# SDriveARM.net
KiCad netlist of a schematic drawn in EAGLE
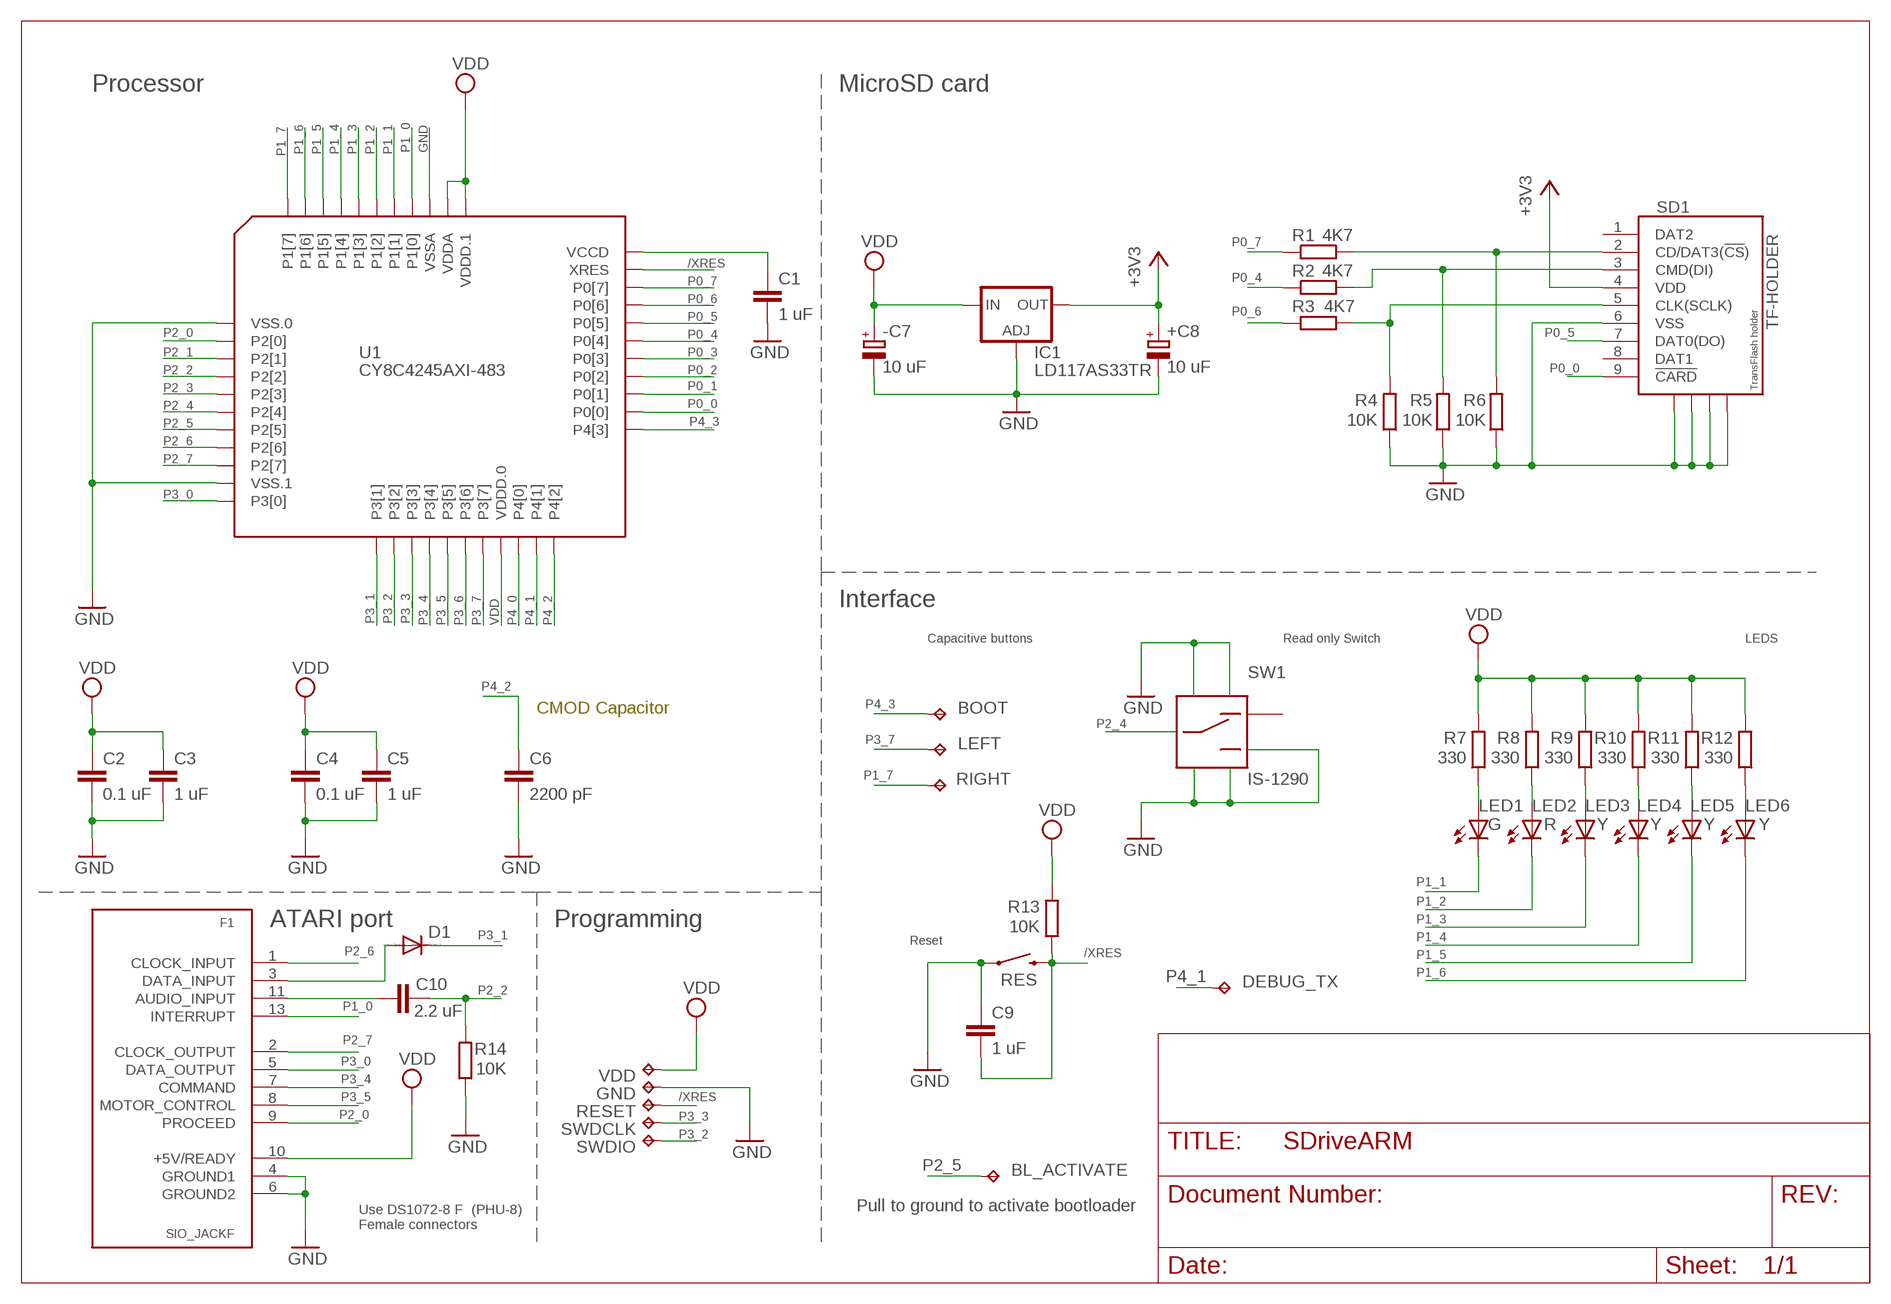
[diagram p0: schematic, sheet 1]

(export (version "E")
  (design (tool "Eeschema 10.0.6"))
  (components
    (comp (ref "+C8")
      (value "10 uF")
      (footprint "eagle-import:A_3216-18W")
      (libsource (lib "eagle-import") (part "CPOL-EUA/3216-18W"))
    )
    (comp (ref "-C7")
      (value "10 uF")
      (footprint "eagle-import:A_3216-18W")
      (libsource (lib "eagle-import") (part "CPOL-EUA/3216-18W"))
    )
    (comp (ref "BL_ACTIVATE")
      (value "TPB1,27")
      (footprint "eagle-import:B1,27")
      (libsource (lib "eagle-import") (part "TPB1,27"))
    )
    (comp (ref "BOOT")
      (value "TPTP20SQ")
      (footprint "eagle-import:TP20SQ")
      (libsource (lib "eagle-import") (part "TPTP20SQ"))
    )
    (comp (ref "C1")
      (value "1 uF")
      (footprint "eagle-import:C0603")
      (libsource (lib "eagle-import") (part "C-EUC0603"))
    )
    (comp (ref "C2")
      (value "0.1 uF")
      (footprint "eagle-import:C0603")
      (libsource (lib "eagle-import") (part "C-EUC0603"))
    )
    (comp (ref "C3")
      (value "1 uF")
      (footprint "eagle-import:C0603")
      (libsource (lib "eagle-import") (part "C-EUC0603"))
    )
    (comp (ref "C4")
      (value "0.1 uF")
      (footprint "eagle-import:C0603")
      (libsource (lib "eagle-import") (part "C-EUC0603"))
    )
    (comp (ref "C5")
      (value "1 uF")
      (footprint "eagle-import:C0603")
      (libsource (lib "eagle-import") (part "C-EUC0603"))
    )
    (comp (ref "C6")
      (value "2200 pF")
      (footprint "eagle-import:C0603")
      (libsource (lib "eagle-import") (part "C-EUC0603"))
    )
    (comp (ref "C9")
      (value "1 uF")
      (footprint "eagle-import:C0603")
      (libsource (lib "eagle-import") (part "C-EUC0603"))
    )
    (comp (ref "C10")
      (value "2.2 uF")
      (footprint "eagle-import:C0603")
      (libsource (lib "eagle-import") (part "C-EUC0603"))
    )
    (comp (ref "D1")
      (value "MBR0520LT")
      (footprint "eagle-import:SOD123")
      (libsource (lib "eagle-import") (part "MBR0520LT"))
    )
    (comp (ref "DEBUG_TX")
      (value "TPB1,27")
      (footprint "eagle-import:B1,27")
      (libsource (lib "eagle-import") (part "TPB1,27"))
    )
    (comp (ref "F1")
      (value "SIO_JACKF")
      (footprint "eagle-import:SIO_JACK_F")
      (libsource (lib "eagle-import") (part "SIO_JACKF"))
    )
    (comp (ref "GND")
      (value "TPB1,27")
      (footprint "eagle-import:B1,27")
      (libsource (lib "eagle-import") (part "TPB1,27"))
    )
    (comp (ref "IC1")
      (value "LD117AS33TR")
      (footprint "eagle-import:SOT223")
      (libsource (lib "eagle-import") (part "LD117A?S33TR"))
    )
    (comp (ref "LED1")
      (value "G")
      (footprint "eagle-import:SML0805")
      (libsource (lib "eagle-import") (part "LEDSML0805"))
    )
    (comp (ref "LED2")
      (value "R")
      (footprint "eagle-import:SML0805")
      (libsource (lib "eagle-import") (part "LEDSML0805"))
    )
    (comp (ref "LED3")
      (value "Y")
      (footprint "eagle-import:SML0805")
      (libsource (lib "eagle-import") (part "LEDSML0805"))
    )
    (comp (ref "LED4")
      (value "Y")
      (footprint "eagle-import:SML0805")
      (libsource (lib "eagle-import") (part "LEDSML0805"))
    )
    (comp (ref "LED5")
      (value "Y")
      (footprint "eagle-import:SML0805")
      (libsource (lib "eagle-import") (part "LEDSML0805"))
    )
    (comp (ref "LED6")
      (value "Y")
      (footprint "eagle-import:SML0805")
      (libsource (lib "eagle-import") (part "LEDSML0805"))
    )
    (comp (ref "LEFT")
      (value "TPTP20SQ")
      (footprint "eagle-import:TP20SQ")
      (libsource (lib "eagle-import") (part "TPTP20SQ"))
    )
    (comp (ref "R1")
      (value "4K7")
      (footprint "eagle-import:R0603")
      (libsource (lib "eagle-import") (part "R-EU_R0603"))
    )
    (comp (ref "R2")
      (value "4K7")
      (footprint "eagle-import:R0603")
      (libsource (lib "eagle-import") (part "R-EU_R0603"))
    )
    (comp (ref "R3")
      (value "4K7")
      (footprint "eagle-import:R0603")
      (libsource (lib "eagle-import") (part "R-EU_R0603"))
    )
    (comp (ref "R4")
      (value "10K")
      (footprint "eagle-import:R0603")
      (libsource (lib "eagle-import") (part "R-EU_R0603"))
    )
    (comp (ref "R5")
      (value "10K")
      (footprint "eagle-import:R0603")
      (libsource (lib "eagle-import") (part "R-EU_R0603"))
    )
    (comp (ref "R6")
      (value "10K")
      (footprint "eagle-import:R0603")
      (libsource (lib "eagle-import") (part "R-EU_R0603"))
    )
    (comp (ref "R7")
      (value "330")
      (footprint "eagle-import:R0603")
      (libsource (lib "eagle-import") (part "R-EU_R0603"))
    )
    (comp (ref "R8")
      (value "330")
      (footprint "eagle-import:R0603")
      (libsource (lib "eagle-import") (part "R-EU_R0603"))
    )
    (comp (ref "R9")
      (value "330")
      (footprint "eagle-import:R0603")
      (libsource (lib "eagle-import") (part "R-EU_R0603"))
    )
    (comp (ref "R10")
      (value "330")
      (footprint "eagle-import:R0603")
      (libsource (lib "eagle-import") (part "R-EU_R0603"))
    )
    (comp (ref "R11")
      (value "330")
      (footprint "eagle-import:R0603")
      (libsource (lib "eagle-import") (part "R-EU_R0603"))
    )
    (comp (ref "R12")
      (value "330")
      (footprint "eagle-import:R0603")
      (libsource (lib "eagle-import") (part "R-EU_R0603"))
    )
    (comp (ref "R13")
      (value "10K")
      (footprint "eagle-import:R0603")
      (libsource (lib "eagle-import") (part "R-EU_R0603"))
    )
    (comp (ref "R14")
      (value "10K")
      (footprint "eagle-import:R0603")
      (libsource (lib "eagle-import") (part "R-EU_R0603"))
    )
    (comp (ref "RES")
      (value "SWITCH-MOMENTARY-2")
      (footprint "eagle-import:TACTILE_SWITCH_TALL")
      (libsource (lib "eagle-import") (part "SWITCH-MOMENTARY-2"))
    )
    (comp (ref "RESET")
      (value "TPB1,27")
      (footprint "eagle-import:B1,27")
      (libsource (lib "eagle-import") (part "TPB1,27"))
    )
    (comp (ref "RIGHT")
      (value "TPTP20SQ")
      (footprint "eagle-import:TP20SQ")
      (libsource (lib "eagle-import") (part "TPTP20SQ"))
    )
    (comp (ref "SD1")
      (value "TF-HOLDER")
      (footprint "eagle-import:TF-PULL")
      (libsource (lib "eagle-import") (part "TF-HOLDER"))
    )
    (comp (ref "SW1")
      (value "IS-1290")
      (footprint "eagle-import:IS-1290")
      (libsource (lib "eagle-import") (part "IS-1290"))
    )
    (comp (ref "SWDCLK")
      (value "TPB1,27")
      (footprint "eagle-import:B1,27")
      (libsource (lib "eagle-import") (part "TPB1,27"))
    )
    (comp (ref "SWDIO")
      (value "TPB1,27")
      (footprint "eagle-import:B1,27")
      (libsource (lib "eagle-import") (part "TPB1,27"))
    )
    (comp (ref "U1")
      (value "CY8C4245AXI-483")
      (footprint "eagle-import:TQFP44")
      (libsource (lib "eagle-import") (part "CY8C4245AXI-483"))
    )
    (comp (ref "VDD")
      (value "TPB1,27")
      (footprint "eagle-import:B1,27")
      (libsource (lib "eagle-import") (part "TPB1,27"))
    )
  )
  (nets
    (net (code "1") (name "+3V3") (class "Default")
      (node (ref "+C8") (pin "+") (pinfunction "+_+") (pintype "passive"))
      (node (ref "IC1") (pin "4") (pinfunction "OUT_4") (pintype "passive"))
      (node (ref "SD1") (pin "4") (pinfunction "VDD_4") (pintype "power_in"))
    )
    (net (code "2") (name "/P0_0") (class "Default")
      (node (ref "SD1") (pin "9") (pinfunction "~{CARD}_9") (pintype "passive"))
      (node (ref "U1") (pin "24") (pinfunction "P0[0]_24") (pintype "bidirectional"))
    )
    (net (code "3") (name "/P0_1") (class "Default")
      (node (ref "U1") (pin "25") (pinfunction "P0[1]_25") (pintype "bidirectional"))
    )
    (net (code "4") (name "/P0_2") (class "Default")
      (node (ref "U1") (pin "26") (pinfunction "P0[2]_26") (pintype "bidirectional"))
    )
    (net (code "5") (name "/P0_3") (class "Default")
      (node (ref "U1") (pin "27") (pinfunction "P0[3]_27") (pintype "bidirectional"))
    )
    (net (code "6") (name "/P0_4") (class "Default")
      (node (ref "R2") (pin "1") (pinfunction "1_1") (pintype "passive"))
      (node (ref "U1") (pin "28") (pinfunction "P0[4]_28") (pintype "bidirectional"))
    )
    (net (code "7") (name "/P0_5") (class "Default")
      (node (ref "SD1") (pin "7") (pinfunction "DAT0(DO)_7") (pintype "bidirectional"))
      (node (ref "U1") (pin "29") (pinfunction "P0[5]_29") (pintype "bidirectional"))
    )
    (net (code "8") (name "/P0_6") (class "Default")
      (node (ref "R3") (pin "1") (pinfunction "1_1") (pintype "passive"))
      (node (ref "U1") (pin "30") (pinfunction "P0[6]_30") (pintype "bidirectional"))
    )
    (net (code "9") (name "/P0_7") (class "Default")
      (node (ref "R1") (pin "1") (pinfunction "1_1") (pintype "passive"))
      (node (ref "U1") (pin "31") (pinfunction "P0[7]_31") (pintype "bidirectional"))
    )
    (net (code "10") (name "/P1_0") (class "Default")
      (node (ref "F1") (pin "13") (pinfunction "INTERRUPT_13") (pintype "output"))
      (node (ref "U1") (pin "37") (pinfunction "P1[0]_37") (pintype "bidirectional"))
    )
    (net (code "11") (name "/P1_1") (class "Default")
      (node (ref "LED1") (pin "C") (pinfunction "C_C") (pintype "passive"))
      (node (ref "U1") (pin "38") (pinfunction "P1[1]_38") (pintype "bidirectional"))
    )
    (net (code "12") (name "/P1_2") (class "Default")
      (node (ref "LED2") (pin "C") (pinfunction "C_C") (pintype "passive"))
      (node (ref "U1") (pin "39") (pinfunction "P1[2]_39") (pintype "bidirectional"))
    )
    (net (code "13") (name "/P1_3") (class "Default")
      (node (ref "LED3") (pin "C") (pinfunction "C_C") (pintype "passive"))
      (node (ref "U1") (pin "40") (pinfunction "P1[3]_40") (pintype "bidirectional"))
    )
    (net (code "14") (name "/P1_4") (class "Default")
      (node (ref "LED4") (pin "C") (pinfunction "C_C") (pintype "passive"))
      (node (ref "U1") (pin "41") (pinfunction "P1[4]_41") (pintype "bidirectional"))
    )
    (net (code "15") (name "/P1_5") (class "Default")
      (node (ref "LED5") (pin "C") (pinfunction "C_C") (pintype "passive"))
      (node (ref "U1") (pin "42") (pinfunction "P1[5]_42") (pintype "bidirectional"))
    )
    (net (code "16") (name "/P1_6") (class "Default")
      (node (ref "LED6") (pin "C") (pinfunction "C_C") (pintype "passive"))
      (node (ref "U1") (pin "43") (pinfunction "P1[6]_43") (pintype "bidirectional"))
    )
    (net (code "17") (name "/P1_7") (class "Default")
      (node (ref "RIGHT") (pin "TP") (pinfunction "TP_TP") (pintype "input"))
      (node (ref "U1") (pin "44") (pinfunction "P1[7]_44") (pintype "bidirectional"))
    )
    (net (code "18") (name "/P2_0") (class "Default")
      (node (ref "F1") (pin "9") (pinfunction "PROCEED_9") (pintype "bidirectional"))
      (node (ref "U1") (pin "2") (pinfunction "P2[0]_2") (pintype "bidirectional"))
    )
    (net (code "19") (name "/P2_1") (class "Default")
      (node (ref "U1") (pin "3") (pinfunction "P2[1]_3") (pintype "bidirectional"))
    )
    (net (code "20") (name "/P2_2") (class "Default")
      (node (ref "C10") (pin "1") (pinfunction "1_1") (pintype "passive"))
      (node (ref "R14") (pin "2") (pinfunction "2_2") (pintype "passive"))
      (node (ref "U1") (pin "4") (pinfunction "P2[2]_4") (pintype "bidirectional"))
    )
    (net (code "21") (name "/P2_3") (class "Default")
      (node (ref "U1") (pin "5") (pinfunction "P2[3]_5") (pintype "bidirectional"))
    )
    (net (code "22") (name "/P2_4") (class "Default")
      (node (ref "SW1") (pin "COMMON") (pinfunction "COMMON_COMMON") (pintype "bidirectional"))
      (node (ref "U1") (pin "6") (pinfunction "P2[4]_6") (pintype "bidirectional"))
    )
    (net (code "23") (name "/P2_5") (class "Default")
      (node (ref "BL_ACTIVATE") (pin "TP") (pinfunction "TP_TP") (pintype "input"))
      (node (ref "U1") (pin "7") (pinfunction "P2[5]_7") (pintype "bidirectional"))
    )
    (net (code "24") (name "/P2_6") (class "Default")
      (node (ref "F1") (pin "1") (pinfunction "CLOCK_INPUT_1") (pintype "output"))
      (node (ref "U1") (pin "8") (pinfunction "P2[6]_8") (pintype "bidirectional"))
    )
    (net (code "25") (name "/P2_7") (class "Default")
      (node (ref "F1") (pin "2") (pinfunction "CLOCK_OUTPUT_2") (pintype "input"))
      (node (ref "U1") (pin "9") (pinfunction "P2[7]_9") (pintype "bidirectional"))
    )
    (net (code "26") (name "/P3_0") (class "Default")
      (node (ref "F1") (pin "5") (pinfunction "DATA_OUTPUT_5") (pintype "input"))
      (node (ref "U1") (pin "11") (pinfunction "P3[0]_11") (pintype "bidirectional"))
    )
    (net (code "27") (name "/P3_1") (class "Default")
      (node (ref "D1") (pin "C") (pinfunction "C_C") (pintype "passive"))
      (node (ref "U1") (pin "12") (pinfunction "P3[1]_12") (pintype "bidirectional"))
    )
    (net (code "28") (name "/P3_2") (class "Default")
      (node (ref "SWDIO") (pin "TP") (pinfunction "TP_TP") (pintype "input"))
      (node (ref "U1") (pin "13") (pinfunction "P3[2]_13") (pintype "bidirectional"))
    )
    (net (code "29") (name "/P3_3") (class "Default")
      (node (ref "SWDCLK") (pin "TP") (pinfunction "TP_TP") (pintype "input"))
      (node (ref "U1") (pin "14") (pinfunction "P3[3]_14") (pintype "bidirectional"))
    )
    (net (code "30") (name "/P3_4") (class "Default")
      (node (ref "F1") (pin "7") (pinfunction "COMMAND_7") (pintype "input"))
      (node (ref "U1") (pin "15") (pinfunction "P3[4]_15") (pintype "bidirectional"))
    )
    (net (code "31") (name "/P3_5") (class "Default")
      (node (ref "F1") (pin "8") (pinfunction "MOTOR_CONTROL_8") (pintype "input"))
      (node (ref "U1") (pin "16") (pinfunction "P3[5]_16") (pintype "bidirectional"))
    )
    (net (code "32") (name "/P3_6") (class "Default")
      (node (ref "U1") (pin "17") (pinfunction "P3[6]_17") (pintype "bidirectional"))
    )
    (net (code "33") (name "/P3_7") (class "Default")
      (node (ref "LEFT") (pin "TP") (pinfunction "TP_TP") (pintype "input"))
      (node (ref "U1") (pin "18") (pinfunction "P3[7]_18") (pintype "bidirectional"))
    )
    (net (code "34") (name "/P4_0") (class "Default")
      (node (ref "U1") (pin "20") (pinfunction "P4[0]_20") (pintype "bidirectional"))
    )
    (net (code "35") (name "/P4_1") (class "Default")
      (node (ref "DEBUG_TX") (pin "TP") (pinfunction "TP_TP") (pintype "input"))
      (node (ref "U1") (pin "21") (pinfunction "P4[1]_21") (pintype "bidirectional"))
    )
    (net (code "36") (name "/P4_2") (class "Default")
      (node (ref "C6") (pin "1") (pinfunction "1_1") (pintype "passive"))
      (node (ref "U1") (pin "22") (pinfunction "P4[2]_22") (pintype "bidirectional"))
    )
    (net (code "37") (name "/P4_3") (class "Default")
      (node (ref "BOOT") (pin "TP") (pinfunction "TP_TP") (pintype "input"))
      (node (ref "U1") (pin "23") (pinfunction "P4[3]_23") (pintype "bidirectional"))
    )
    (net (code "38") (name "/{slash}XRES") (class "Default")
      (node (ref "C9") (pin "2") (pinfunction "2_2") (pintype "passive"))
      (node (ref "R13") (pin "1") (pinfunction "1_1") (pintype "passive"))
      (node (ref "RES") (pin "B2") (pinfunction "2_B2") (pintype "passive"))
      (node (ref "RESET") (pin "TP") (pinfunction "TP_TP") (pintype "input"))
      (node (ref "U1") (pin "32") (pinfunction "XRES_32") (pintype "bidirectional"))
    )
    (net (code "39") (name "GND") (class "Default")
      (node (ref "+C8") (pin "-") (pinfunction "-_-") (pintype "passive"))
      (node (ref "-C7") (pin "-") (pinfunction "-_-") (pintype "passive"))
      (node (ref "C1") (pin "2") (pinfunction "2_2") (pintype "passive"))
      (node (ref "C2") (pin "2") (pinfunction "2_2") (pintype "passive"))
      (node (ref "C3") (pin "2") (pinfunction "2_2") (pintype "passive"))
      (node (ref "C4") (pin "2") (pinfunction "2_2") (pintype "passive"))
      (node (ref "C5") (pin "2") (pinfunction "2_2") (pintype "passive"))
      (node (ref "C6") (pin "2") (pinfunction "2_2") (pintype "passive"))
      (node (ref "C9") (pin "1") (pinfunction "1_1") (pintype "passive"))
      (node (ref "F1") (pin "4") (pinfunction "GROUND1_4") (pintype "power_in"))
      (node (ref "F1") (pin "6") (pinfunction "GROUND2_6") (pintype "power_in"))
      (node (ref "GND") (pin "TP") (pinfunction "TP_TP") (pintype "input"))
      (node (ref "IC1") (pin "1") (pinfunction "ADJ_1") (pintype "input"))
      (node (ref "R14") (pin "1") (pinfunction "1_1") (pintype "passive"))
      (node (ref "R4") (pin "1") (pinfunction "1_1") (pintype "passive"))
      (node (ref "R5") (pin "1") (pinfunction "1_1") (pintype "passive"))
      (node (ref "R6") (pin "1") (pinfunction "1_1") (pintype "passive"))
      (node (ref "RES") (pin "A2") (pinfunction "1_A2") (pintype "passive"))
      (node (ref "SD1") (pin "6") (pinfunction "VSS_6") (pintype "power_in"))
      (node (ref "SD1") (pin "S1") (pinfunction "S1_S1") (pintype "passive"))
      (node (ref "SD1") (pin "S2") (pinfunction "S2_S2") (pintype "passive"))
      (node (ref "SD1") (pin "S3") (pinfunction "S3_S3") (pintype "passive"))
      (node (ref "SD1") (pin "S4") (pinfunction "S4_S4") (pintype "passive"))
      (node (ref "SW1") (pin "POS2") (pinfunction "POS2_POS2") (pintype "bidirectional"))
      (node (ref "SW1") (pin "SHIELD$1") (pinfunction "P$4_SHIELD$1") (pintype "bidirectional"))
      (node (ref "SW1") (pin "SHIELD$2") (pinfunction "P$7_SHIELD$2") (pintype "bidirectional"))
      (node (ref "SW1") (pin "SHIELD$3") (pinfunction "P$5_SHIELD$3") (pintype "bidirectional"))
      (node (ref "SW1") (pin "SHIELD$4") (pinfunction "P$6_SHIELD$4") (pintype "bidirectional"))
      (node (ref "U1") (pin "1") (pinfunction "VSS.0_1") (pintype "power_in"))
      (node (ref "U1") (pin "10") (pinfunction "VSS.1_10") (pintype "power_in"))
      (node (ref "U1") (pin "36") (pinfunction "VSSA_36") (pintype "power_in"))
    )
    (net (code "40") (name "Net-(F1-AUDIO_INPUT)") (class "Default")
      (node (ref "C10") (pin "2") (pinfunction "2_2") (pintype "passive"))
      (node (ref "F1") (pin "11") (pinfunction "AUDIO_INPUT_11") (pintype "output"))
    )
    (net (code "41") (name "Net-(F1-DATA_INPUT)") (class "Default")
      (node (ref "D1") (pin "A") (pinfunction "A_A") (pintype "passive"))
      (node (ref "F1") (pin "3") (pinfunction "DATA_INPUT_3") (pintype "output"))
    )
    (net (code "42") (name "Net-(LED1-PadA)") (class "Default")
      (node (ref "LED1") (pin "A") (pinfunction "A_A") (pintype "passive"))
      (node (ref "R7") (pin "1") (pinfunction "1_1") (pintype "passive"))
    )
    (net (code "43") (name "Net-(LED2-PadA)") (class "Default")
      (node (ref "LED2") (pin "A") (pinfunction "A_A") (pintype "passive"))
      (node (ref "R8") (pin "1") (pinfunction "1_1") (pintype "passive"))
    )
    (net (code "44") (name "Net-(LED3-PadA)") (class "Default")
      (node (ref "LED3") (pin "A") (pinfunction "A_A") (pintype "passive"))
      (node (ref "R9") (pin "1") (pinfunction "1_1") (pintype "passive"))
    )
    (net (code "45") (name "Net-(LED4-PadA)") (class "Default")
      (node (ref "LED4") (pin "A") (pinfunction "A_A") (pintype "passive"))
      (node (ref "R10") (pin "1") (pinfunction "1_1") (pintype "passive"))
    )
    (net (code "46") (name "Net-(LED5-PadA)") (class "Default")
      (node (ref "LED5") (pin "A") (pinfunction "A_A") (pintype "passive"))
      (node (ref "R11") (pin "1") (pinfunction "1_1") (pintype "passive"))
    )
    (net (code "47") (name "Net-(LED6-PadA)") (class "Default")
      (node (ref "LED6") (pin "A") (pinfunction "A_A") (pintype "passive"))
      (node (ref "R12") (pin "1") (pinfunction "1_1") (pintype "passive"))
    )
    (net (code "48") (name "Net-(SD1-CD{slash}DAT3(~{CS}))") (class "Default")
      (node (ref "R1") (pin "2") (pinfunction "2_2") (pintype "passive"))
      (node (ref "R6") (pin "2") (pinfunction "2_2") (pintype "passive"))
      (node (ref "SD1") (pin "2") (pinfunction "CD/DAT3(~{CS})_2") (pintype "bidirectional"))
    )
    (net (code "49") (name "Net-(SD1-CLK(SCLK))") (class "Default")
      (node (ref "R3") (pin "2") (pinfunction "2_2") (pintype "passive"))
      (node (ref "R4") (pin "2") (pinfunction "2_2") (pintype "passive"))
      (node (ref "SD1") (pin "5") (pinfunction "CLK(SCLK)_5") (pintype "input"))
    )
    (net (code "50") (name "Net-(SD1-CMD(DI))") (class "Default")
      (node (ref "R2") (pin "2") (pinfunction "2_2") (pintype "passive"))
      (node (ref "R5") (pin "2") (pinfunction "2_2") (pintype "passive"))
      (node (ref "SD1") (pin "3") (pinfunction "CMD(DI)_3") (pintype "bidirectional"))
    )
    (net (code "51") (name "Net-(U1-VCCD)") (class "Default")
      (node (ref "C1") (pin "1") (pinfunction "1_1") (pintype "passive"))
      (node (ref "U1") (pin "33") (pinfunction "VCCD_33") (pintype "power_in"))
    )
    (net (code "52") (name "VDD") (class "Default")
      (node (ref "-C7") (pin "+") (pinfunction "+_+") (pintype "passive"))
      (node (ref "C2") (pin "1") (pinfunction "1_1") (pintype "passive"))
      (node (ref "C3") (pin "1") (pinfunction "1_1") (pintype "passive"))
      (node (ref "C4") (pin "1") (pinfunction "1_1") (pintype "passive"))
      (node (ref "C5") (pin "1") (pinfunction "1_1") (pintype "passive"))
      (node (ref "F1") (pin "10") (pinfunction "+5V/READY_10") (pintype "power_in"))
      (node (ref "IC1") (pin "3") (pinfunction "IN_3") (pintype "input"))
      (node (ref "R10") (pin "2") (pinfunction "2_2") (pintype "passive"))
      (node (ref "R11") (pin "2") (pinfunction "2_2") (pintype "passive"))
      (node (ref "R12") (pin "2") (pinfunction "2_2") (pintype "passive"))
      (node (ref "R13") (pin "2") (pinfunction "2_2") (pintype "passive"))
      (node (ref "R7") (pin "2") (pinfunction "2_2") (pintype "passive"))
      (node (ref "R8") (pin "2") (pinfunction "2_2") (pintype "passive"))
      (node (ref "R9") (pin "2") (pinfunction "2_2") (pintype "passive"))
      (node (ref "U1") (pin "19") (pinfunction "VDDD.0_19") (pintype "power_in"))
      (node (ref "U1") (pin "34") (pinfunction "VDDD.1_34") (pintype "power_in"))
      (node (ref "U1") (pin "35") (pinfunction "VDDA_35") (pintype "power_in"))
      (node (ref "VDD") (pin "TP") (pinfunction "TP_TP") (pintype "input"))
    )
    (net (code "53") (name "unconnected-(SD1-DAT1-Pad8)") (class "Default")
      (node (ref "SD1") (pin "8") (pinfunction "DAT1_8") (pintype "bidirectional"))
    )
    (net (code "54") (name "unconnected-(SD1-DAT2-Pad1)") (class "Default")
      (node (ref "SD1") (pin "1") (pinfunction "DAT2_1") (pintype "bidirectional"))
    )
    (net (code "55") (name "unconnected-(SW1-PadPOS1)") (class "Default")
      (node (ref "SW1") (pin "POS1") (pinfunction "POS1_POS1") (pintype "bidirectional"))
    )
  )
)
